# DataLoggerV2.net
KiCad netlist of a schematic drawn in EAGLE
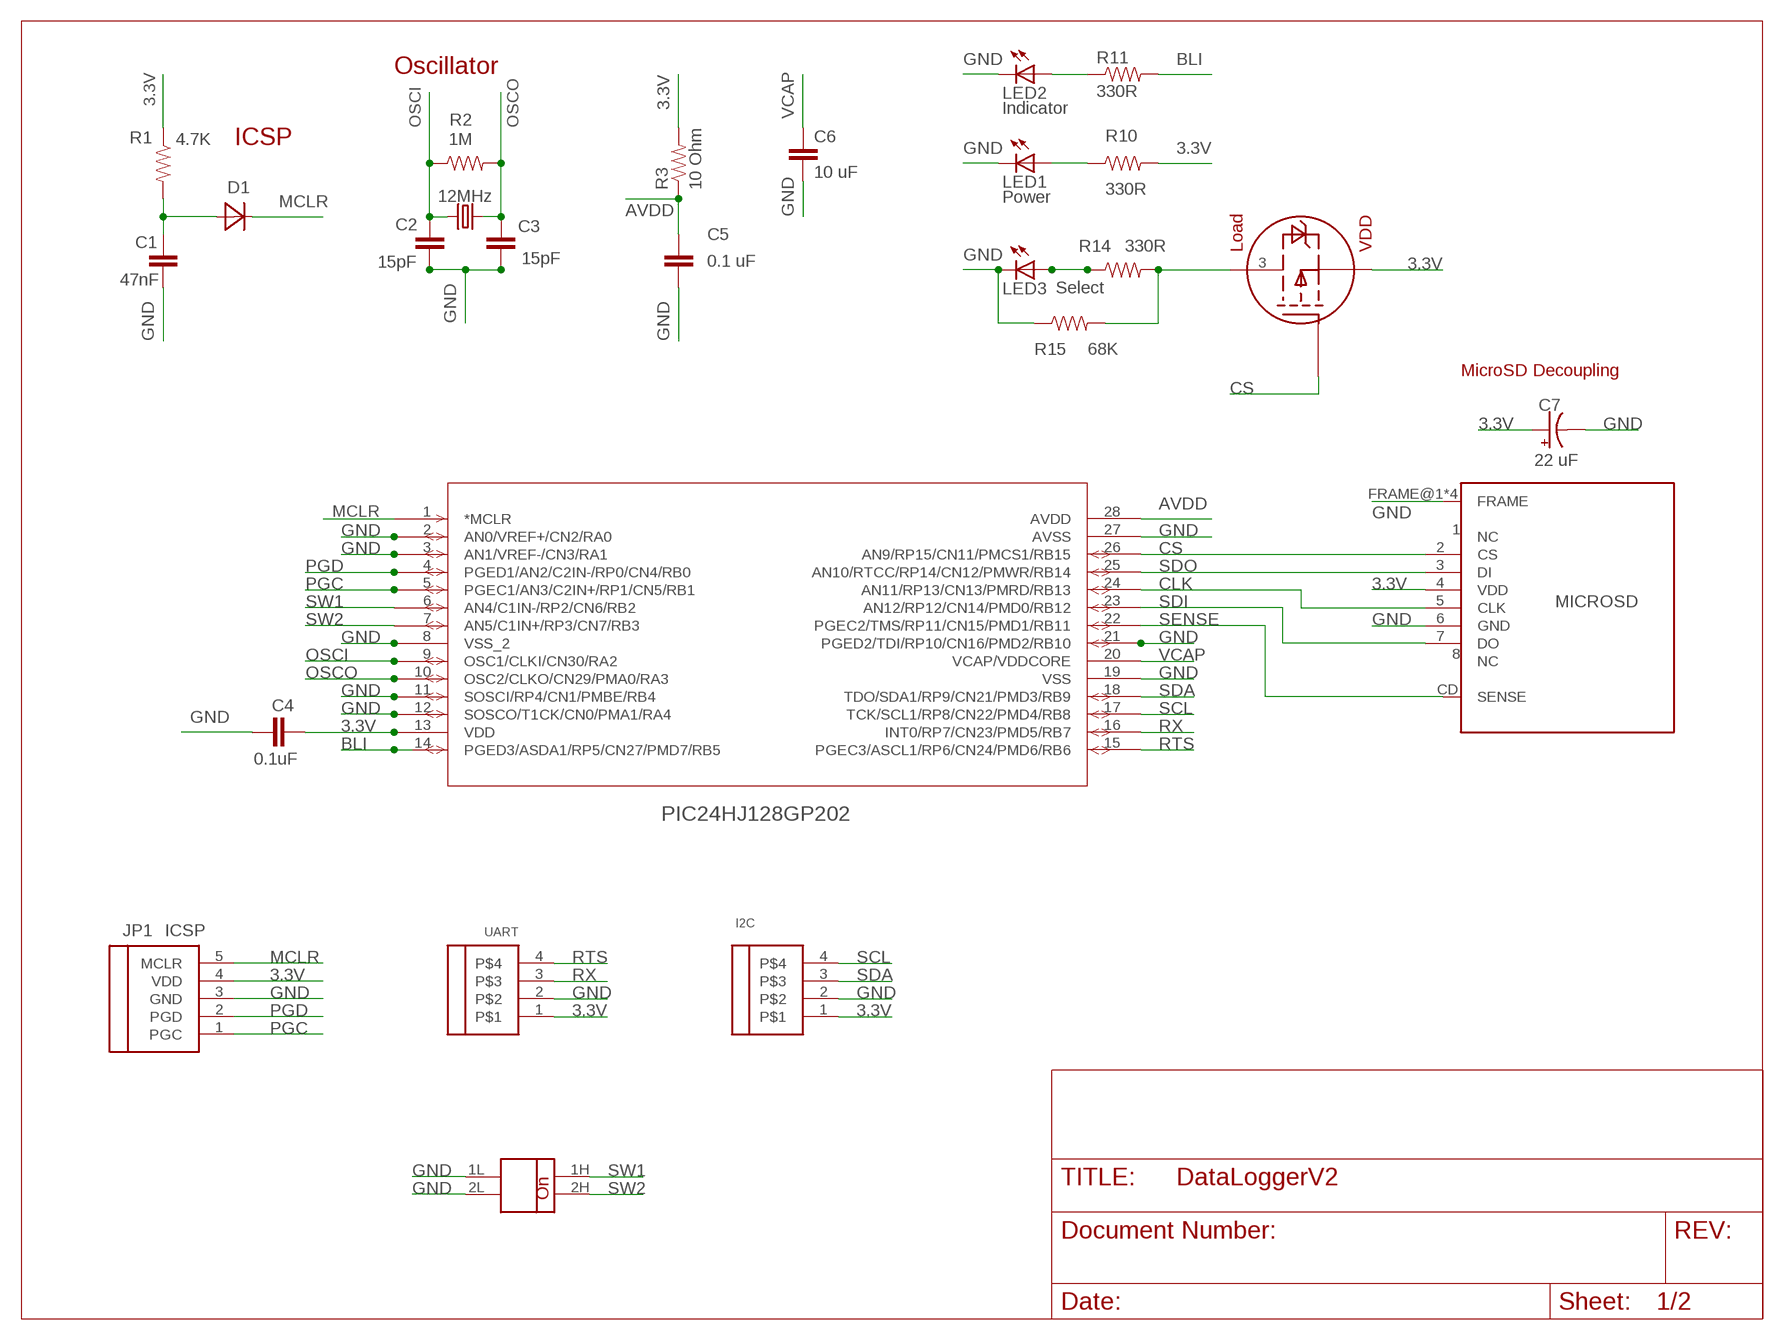
[diagram p0: schematic, sheet 1]
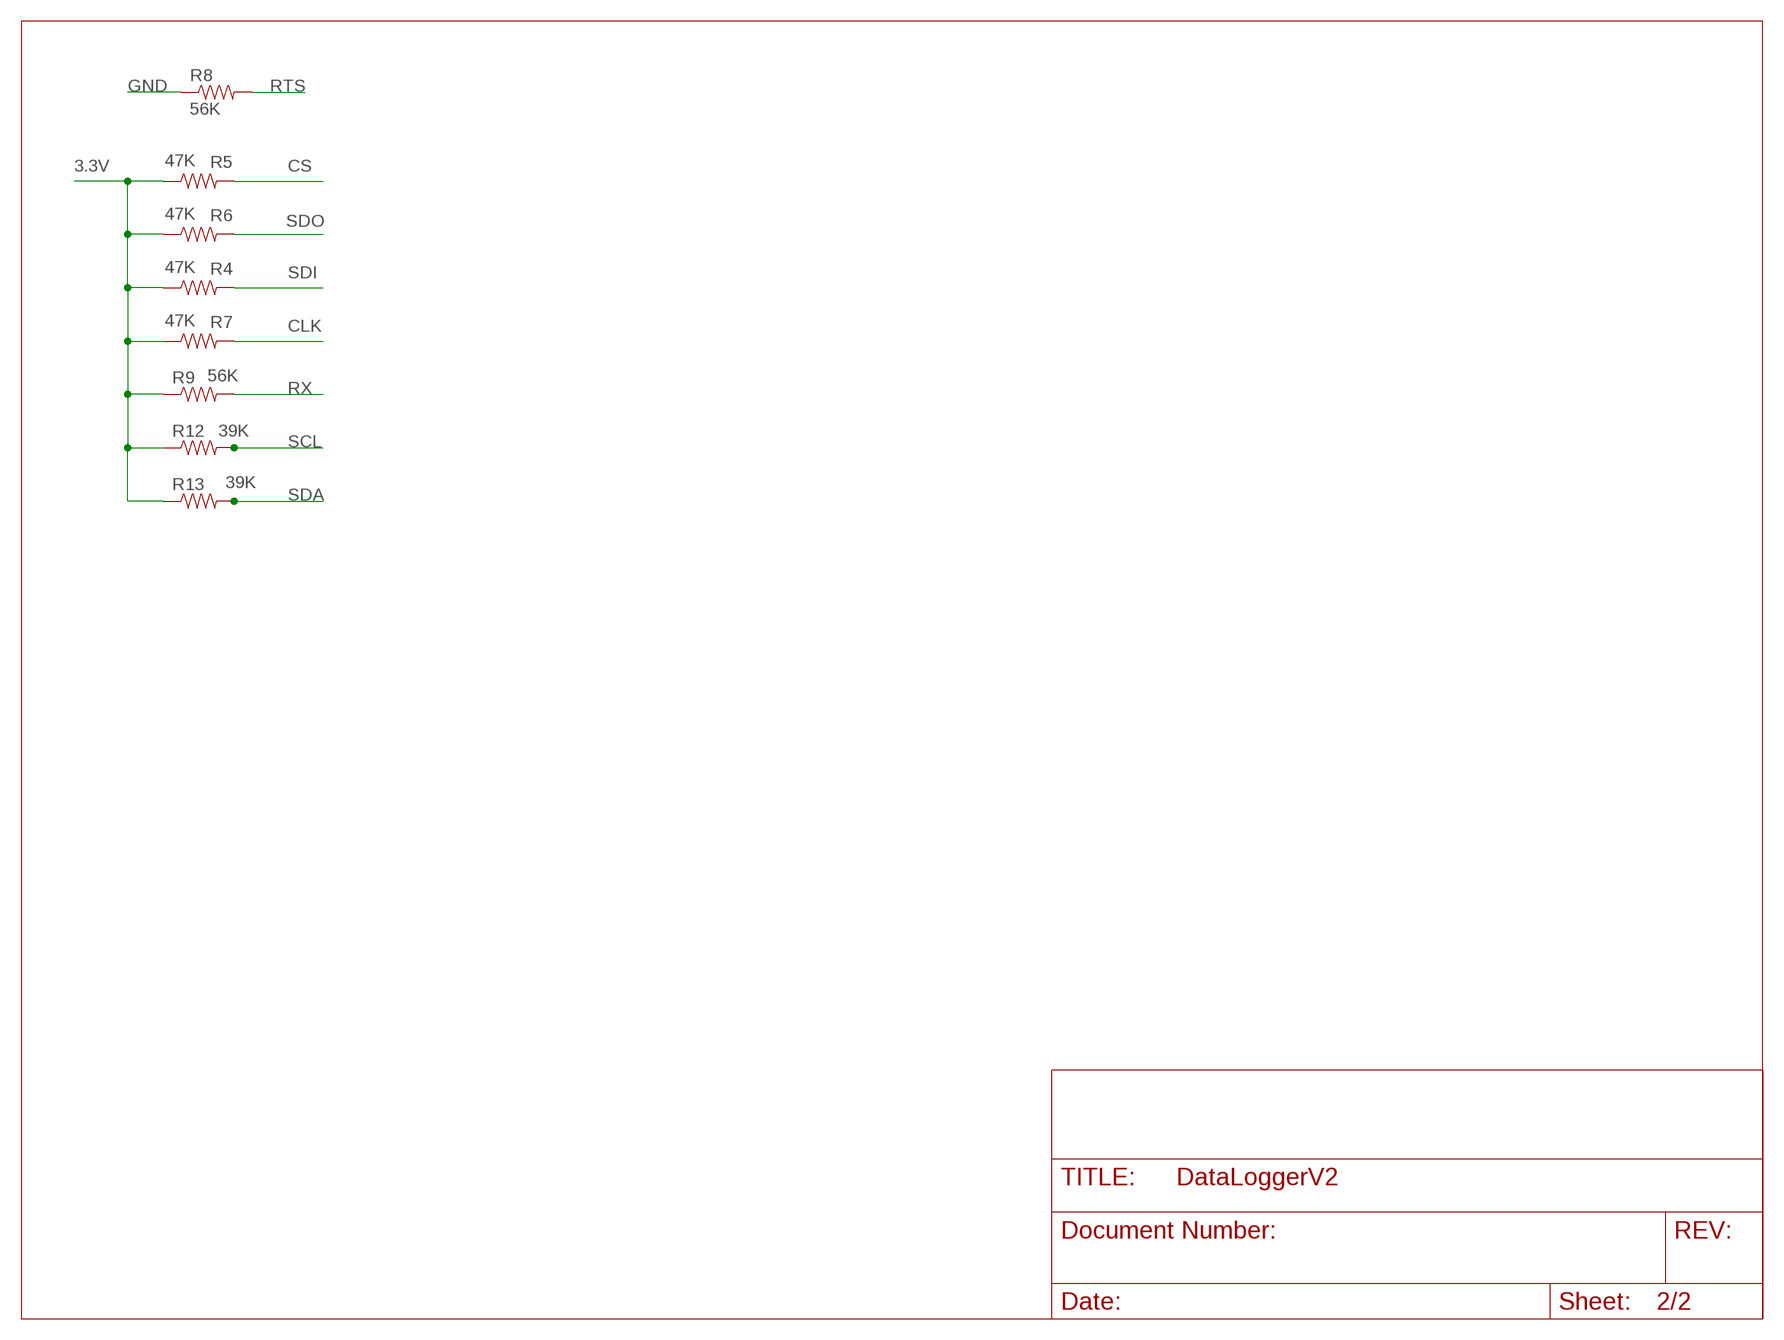
[diagram p1: schematic, sheet 2]

(export (version "E")
  (design (tool "Eeschema 10.0.6"))
  (components
    (comp (ref "C1")
      (value "47nF")
      (footprint "eagle-import:0805_INCH-HS-CAP")
      (libsource (lib "eagle-import") (part "CAP-CERAMIC_0805"))
    )
    (comp (ref "C2")
      (value "15pF")
      (footprint "eagle-import:0805_INCH-HS-CAP")
      (libsource (lib "eagle-import") (part "CAP-CERAMIC_0805"))
    )
    (comp (ref "C3")
      (value "15pF")
      (footprint "eagle-import:0805_INCH-HS-CAP")
      (libsource (lib "eagle-import") (part "CAP-CERAMIC_0805"))
    )
    (comp (ref "C4")
      (value "0.1uF")
      (footprint "eagle-import:0603_INCH-HS-CAP")
      (libsource (lib "eagle-import") (part "CAP-CERAMIC_0603"))
    )
    (comp (ref "C5")
      (value "0.1 uF")
      (footprint "eagle-import:0603_INCH-HS-CAP")
      (libsource (lib "eagle-import") (part "CAP-CERAMIC_0603"))
    )
    (comp (ref "C6")
      (value "10 uF")
      (footprint "eagle-import:1210_INCH-HS-CAP")
      (libsource (lib "eagle-import") (part "CAP-CERAMIC_1210"))
    )
    (comp (ref "C7")
      (value "22 uF")
      (footprint "eagle-import:TANT-C-6032")
      (libsource (lib "eagle-import") (part "CAP-SMD-TANT_C-6032"))
    )
    (comp (ref "D1")
      (value "DIODE_1206")
      (footprint "eagle-import:1206_INCH-HS-DIODE")
      (libsource (lib "eagle-import") (part "DIODE_1206"))
    )
    (comp (ref "I2C")
      (value "HEADER-04_JST-ZH_JST-ZH")
      (footprint "eagle-import:1X04-JST-ZH")
      (libsource (lib "eagle-import") (part "HEADER-04_JST-ZH_JST-ZH"))
    )
    (comp (ref "JP1")
      (value "ICSP")
      (footprint "eagle-import:1X05-JST-ZH")
      (libsource (lib "eagle-import") (part "ICSP_JST-ZH"))
    )
    (comp (ref "LED1")
      (value "Power")
      (footprint "eagle-import:1206_INCH-HS-LED")
      (libsource (lib "eagle-import") (part "LED_SMD_1206"))
    )
    (comp (ref "LED2")
      (value "Indicator")
      (footprint "eagle-import:1206_INCH-HS-LED")
      (libsource (lib "eagle-import") (part "LED_SMD_1206"))
    )
    (comp (ref "LED3")
      (value "Select")
      (footprint "eagle-import:1206_INCH-HS-LED")
      (libsource (lib "eagle-import") (part "LED_SMD_1206"))
    )
    (comp (ref "P-FET")
      (value "NTS2101P")
      (footprint "eagle-import:SOT-323-0NSEMI")
      (libsource (lib "eagle-import") (part "P-MOSFET_SOT323-ONSEMI"))
    )
    (comp (ref "Q1")
      (value "12MHz")
      (footprint "eagle-import:CRYSTAL-SMD-5.0X3.2")
      (libsource (lib "eagle-import") (part "CRYSTAL_SMD-5.0X3.2"))
    )
    (comp (ref "R1")
      (value "4.7K")
      (footprint "eagle-import:0805_INCH-HS")
      (libsource (lib "eagle-import") (part "RESISTOR_0805"))
    )
    (comp (ref "R2")
      (value "1M")
      (footprint "eagle-import:0805_INCH-HS")
      (libsource (lib "eagle-import") (part "RESISTOR_0805"))
    )
    (comp (ref "R3")
      (value "10 Ohm")
      (footprint "eagle-import:0805_INCH-HS")
      (libsource (lib "eagle-import") (part "RESISTOR_0805"))
    )
    (comp (ref "R10")
      (value "330R")
      (footprint "eagle-import:0805_INCH-HS")
      (libsource (lib "eagle-import") (part "RESISTOR_0805"))
    )
    (comp (ref "R11")
      (value "330R")
      (footprint "eagle-import:0805_INCH-HS")
      (libsource (lib "eagle-import") (part "RESISTOR_0805"))
    )
    (comp (ref "R14")
      (value "330R")
      (footprint "eagle-import:0805_INCH-HS")
      (libsource (lib "eagle-import") (part "RESISTOR_0805"))
    )
    (comp (ref "R15")
      (value "68K")
      (footprint "eagle-import:0805_INCH-HS")
      (libsource (lib "eagle-import") (part "RESISTOR_0805"))
    )
    (comp (ref "U$1")
      (value "PIC24HJ128GP202")
      (footprint "eagle-import:SOIC28-W_MC")
      (libsource (lib "eagle-import") (part "PIC24HJ128GP202"))
    )
    (comp (ref "U$2")
      (value "MICROSD")
      (footprint "eagle-import:MICROSD_V1")
      (libsource (lib "eagle-import") (part "MICROSD"))
    )
    (comp (ref "U$3")
      (value "SWITCH-2_HALF-PITCH")
      (footprint "eagle-import:DIP-2-HP")
      (libsource (lib "eagle-import") (part "SWITCH-2_HALF-PITCH"))
    )
    (comp (ref "UART")
      (value "HEADER-04_JST-ZH_JST-ZH")
      (footprint "eagle-import:1X04-JST-ZH")
      (libsource (lib "eagle-import") (part "HEADER-04_JST-ZH_JST-ZH"))
    )
    (comp (ref "R4")
      (value "47K")
      (footprint "eagle-import:0805_INCH-HS")
      (libsource (lib "eagle-import") (part "RESISTOR_0805"))
    )
    (comp (ref "R5")
      (value "47K")
      (footprint "eagle-import:0805_INCH-HS")
      (libsource (lib "eagle-import") (part "RESISTOR_0805"))
    )
    (comp (ref "R6")
      (value "47K")
      (footprint "eagle-import:0805_INCH-HS")
      (libsource (lib "eagle-import") (part "RESISTOR_0805"))
    )
    (comp (ref "R7")
      (value "47K")
      (footprint "eagle-import:0805_INCH-HS")
      (libsource (lib "eagle-import") (part "RESISTOR_0805"))
    )
    (comp (ref "R8")
      (value "56K")
      (footprint "eagle-import:0805_INCH-HS")
      (libsource (lib "eagle-import") (part "RESISTOR_0805"))
    )
    (comp (ref "R9")
      (value "56K")
      (footprint "eagle-import:0805_INCH-HS")
      (libsource (lib "eagle-import") (part "RESISTOR_0805"))
    )
    (comp (ref "R12")
      (value "39K")
      (footprint "eagle-import:0805_INCH-HS")
      (libsource (lib "eagle-import") (part "RESISTOR_0805"))
    )
    (comp (ref "R13")
      (value "39K")
      (footprint "eagle-import:0805_INCH-HS")
      (libsource (lib "eagle-import") (part "RESISTOR_0805"))
    )
  )
  (nets
    (net (code "1") (name "3.3V") (class "Default")
      (node (ref "C4") (pin "1") (pinfunction "1_1") (pintype "passive"))
      (node (ref "C7") (pin "+") (pinfunction "+_+") (pintype "passive"))
      (node (ref "I2C") (pin "1") (pinfunction "P$1_1") (pintype "bidirectional"))
      (node (ref "JP1") (pin "4") (pinfunction "VDD_4") (pintype "bidirectional"))
      (node (ref "P-FET") (pin "2") (pinfunction "S_2") (pintype "bidirectional"))
      (node (ref "R1") (pin "1") (pinfunction "1_1") (pintype "passive"))
      (node (ref "R10") (pin "2") (pinfunction "2_2") (pintype "passive"))
      (node (ref "R12") (pin "1") (pinfunction "1_1") (pintype "passive"))
      (node (ref "R13") (pin "1") (pinfunction "1_1") (pintype "passive"))
      (node (ref "R3") (pin "2") (pinfunction "2_2") (pintype "passive"))
      (node (ref "R4") (pin "1") (pinfunction "1_1") (pintype "passive"))
      (node (ref "R5") (pin "1") (pinfunction "1_1") (pintype "passive"))
      (node (ref "R6") (pin "1") (pinfunction "1_1") (pintype "passive"))
      (node (ref "R7") (pin "1") (pinfunction "1_1") (pintype "passive"))
      (node (ref "R9") (pin "1") (pinfunction "1_1") (pintype "passive"))
      (node (ref "U$1") (pin "13") (pinfunction "VDD_13") (pintype "passive"))
      (node (ref "U$2") (pin "4") (pinfunction "VDD_4") (pintype "power_in"))
      (node (ref "UART") (pin "1") (pinfunction "P$1_1") (pintype "bidirectional"))
    )
    (net (code "2") (name "AVDD") (class "Default")
      (node (ref "C5") (pin "1") (pinfunction "1_1") (pintype "passive"))
      (node (ref "R3") (pin "1") (pinfunction "1_1") (pintype "passive"))
      (node (ref "U$1") (pin "28") (pinfunction "AVDD_28") (pintype "passive"))
    )
    (net (code "3") (name "BLI") (class "Default")
      (node (ref "R11") (pin "2") (pinfunction "2_2") (pintype "passive"))
      (node (ref "U$1") (pin "14") (pinfunction "PGED3/ASDA1/RP5/CN27/PMD7/RB5_14") (pintype "passive"))
    )
    (net (code "4") (name "CLK") (class "Default")
      (node (ref "R7") (pin "2") (pinfunction "2_2") (pintype "passive"))
      (node (ref "U$1") (pin "24") (pinfunction "AN11/RP13/CN13/PMRD/RB13_24") (pintype "passive"))
      (node (ref "U$2") (pin "5") (pinfunction "CLK_5") (pintype "input"))
    )
    (net (code "5") (name "CS") (class "Default")
      (node (ref "P-FET") (pin "1") (pinfunction "G_1") (pintype "input"))
      (node (ref "R5") (pin "2") (pinfunction "2_2") (pintype "passive"))
      (node (ref "U$1") (pin "26") (pinfunction "AN9/RP15/CN11/PMCS1/RB15_26") (pintype "passive"))
      (node (ref "U$2") (pin "2") (pinfunction "CS_2") (pintype "input"))
    )
    (net (code "6") (name "GND") (class "Default")
      (node (ref "C1") (pin "2") (pinfunction "2_2") (pintype "passive"))
      (node (ref "C2") (pin "1") (pinfunction "1_1") (pintype "passive"))
      (node (ref "C3") (pin "1") (pinfunction "1_1") (pintype "passive"))
      (node (ref "C4") (pin "2") (pinfunction "2_2") (pintype "passive"))
      (node (ref "C5") (pin "2") (pinfunction "2_2") (pintype "passive"))
      (node (ref "C6") (pin "P$2") (pinfunction "2_P$2") (pintype "passive"))
      (node (ref "C7") (pin "-") (pinfunction "-_-") (pintype "passive"))
      (node (ref "I2C") (pin "2") (pinfunction "P$2_2") (pintype "bidirectional"))
      (node (ref "JP1") (pin "3") (pinfunction "GND_3") (pintype "bidirectional"))
      (node (ref "LED1") (pin "C") (pinfunction "C_C") (pintype "passive"))
      (node (ref "LED2") (pin "C") (pinfunction "C_C") (pintype "passive"))
      (node (ref "LED3") (pin "C") (pinfunction "C_C") (pintype "passive"))
      (node (ref "R15") (pin "1") (pinfunction "1_1") (pintype "passive"))
      (node (ref "R8") (pin "1") (pinfunction "1_1") (pintype "passive"))
      (node (ref "U$1") (pin "11") (pinfunction "SOSCI/RP4/CN1/PMBE/RB4_11") (pintype "passive"))
      (node (ref "U$1") (pin "12") (pinfunction "SOSCO/T1CK/CN0/PMA1/RA4_12") (pintype "passive"))
      (node (ref "U$1") (pin "19") (pinfunction "VSS_19") (pintype "passive"))
      (node (ref "U$1") (pin "2") (pinfunction "AN0/VREF+/CN2/RA0_2") (pintype "passive"))
      (node (ref "U$1") (pin "21") (pinfunction "PGED2/TDI/RP10/CN16/PMD2/RB10_21") (pintype "passive"))
      (node (ref "U$1") (pin "27") (pinfunction "AVSS_27") (pintype "passive"))
      (node (ref "U$1") (pin "3") (pinfunction "AN1/VREF-/CN3/RA1_3") (pintype "passive"))
      (node (ref "U$1") (pin "8") (pinfunction "VSS_2_8") (pintype "passive"))
      (node (ref "U$2") (pin "6") (pinfunction "GND_6") (pintype "power_in"))
      (node (ref "U$2") (pin "FRAME@1") (pinfunction "FRAME_FRAME@1") (pintype "power_in"))
      (node (ref "U$2") (pin "FRAME@2") (pinfunction "FRAME_FRAME@2") (pintype "power_in"))
      (node (ref "U$2") (pin "FRAME@3") (pinfunction "FRAME_FRAME@3") (pintype "power_in"))
      (node (ref "U$2") (pin "FRAME@4") (pinfunction "FRAME_FRAME@4") (pintype "power_in"))
      (node (ref "U$3") (pin "1L") (pinfunction "1L_1L") (pintype "bidirectional"))
      (node (ref "U$3") (pin "2L") (pinfunction "2L_2L") (pintype "bidirectional"))
      (node (ref "UART") (pin "2") (pinfunction "P$2_2") (pintype "bidirectional"))
    )
    (net (code "7") (name "MCLR") (class "Default")
      (node (ref "D1") (pin "C") (pinfunction "C_C") (pintype "passive"))
      (node (ref "JP1") (pin "5") (pinfunction "MCLR_5") (pintype "bidirectional"))
      (node (ref "U$1") (pin "1") (pinfunction "*MCLR_1") (pintype "passive"))
    )
    (net (code "8") (name "Net-(C1-Pad1)") (class "Default")
      (node (ref "C1") (pin "1") (pinfunction "1_1") (pintype "passive"))
      (node (ref "D1") (pin "A") (pinfunction "A_A") (pintype "passive"))
      (node (ref "R1") (pin "2") (pinfunction "2_2") (pintype "passive"))
    )
    (net (code "9") (name "Net-(LED1-PadA)") (class "Default")
      (node (ref "LED1") (pin "A") (pinfunction "A_A") (pintype "passive"))
      (node (ref "R10") (pin "1") (pinfunction "1_1") (pintype "passive"))
    )
    (net (code "10") (name "Net-(LED2-PadA)") (class "Default")
      (node (ref "LED2") (pin "A") (pinfunction "A_A") (pintype "passive"))
      (node (ref "R11") (pin "1") (pinfunction "1_1") (pintype "passive"))
    )
    (net (code "11") (name "Net-(LED3-PadA)") (class "Default")
      (node (ref "LED3") (pin "A") (pinfunction "A_A") (pintype "passive"))
      (node (ref "R14") (pin "1") (pinfunction "1_1") (pintype "passive"))
    )
    (net (code "12") (name "Net-(P-FET-D)") (class "Default")
      (node (ref "P-FET") (pin "3") (pinfunction "D_3") (pintype "bidirectional"))
      (node (ref "R14") (pin "2") (pinfunction "2_2") (pintype "passive"))
      (node (ref "R15") (pin "2") (pinfunction "2_2") (pintype "passive"))
    )
    (net (code "13") (name "OSCI") (class "Default")
      (node (ref "C2") (pin "2") (pinfunction "2_2") (pintype "passive"))
      (node (ref "Q1") (pin "P$2") (pinfunction "2_P$2") (pintype "passive"))
      (node (ref "R2") (pin "1") (pinfunction "1_1") (pintype "passive"))
      (node (ref "U$1") (pin "9") (pinfunction "OSC1/CLKI/CN30/RA2_9") (pintype "passive"))
    )
    (net (code "14") (name "OSCO") (class "Default")
      (node (ref "C3") (pin "2") (pinfunction "2_2") (pintype "passive"))
      (node (ref "Q1") (pin "P$1") (pinfunction "1_P$1") (pintype "passive"))
      (node (ref "R2") (pin "2") (pinfunction "2_2") (pintype "passive"))
      (node (ref "U$1") (pin "10") (pinfunction "OSC2/CLKO/CN29/PMA0/RA3_10") (pintype "passive"))
    )
    (net (code "15") (name "PGC") (class "Default")
      (node (ref "JP1") (pin "1") (pinfunction "PGC_1") (pintype "bidirectional"))
      (node (ref "U$1") (pin "5") (pinfunction "PGEC1/AN3/C2IN+/RP1/CN5/RB1_5") (pintype "passive"))
    )
    (net (code "16") (name "PGD") (class "Default")
      (node (ref "JP1") (pin "2") (pinfunction "PGD_2") (pintype "bidirectional"))
      (node (ref "U$1") (pin "4") (pinfunction "PGED1/AN2/C2IN-/RP0/CN4/RB0_4") (pintype "passive"))
    )
    (net (code "17") (name "RTS") (class "Default")
      (node (ref "R8") (pin "2") (pinfunction "2_2") (pintype "passive"))
      (node (ref "U$1") (pin "15") (pinfunction "PGEC3/ASCL1/RP6/CN24/PMD6/RB6_15") (pintype "passive"))
      (node (ref "UART") (pin "4") (pinfunction "P$4_4") (pintype "bidirectional"))
    )
    (net (code "18") (name "RX") (class "Default")
      (node (ref "R9") (pin "2") (pinfunction "2_2") (pintype "passive"))
      (node (ref "U$1") (pin "16") (pinfunction "INT0/RP7/CN23/PMD5/RB7_16") (pintype "passive"))
      (node (ref "UART") (pin "3") (pinfunction "P$3_3") (pintype "bidirectional"))
    )
    (net (code "19") (name "SCL") (class "Default")
      (node (ref "I2C") (pin "4") (pinfunction "P$4_4") (pintype "bidirectional"))
      (node (ref "R12") (pin "2") (pinfunction "2_2") (pintype "passive"))
      (node (ref "U$1") (pin "17") (pinfunction "TCK/SCL1/RP8/CN22/PMD4/RB8_17") (pintype "passive"))
    )
    (net (code "20") (name "SDA") (class "Default")
      (node (ref "I2C") (pin "3") (pinfunction "P$3_3") (pintype "bidirectional"))
      (node (ref "R13") (pin "2") (pinfunction "2_2") (pintype "passive"))
      (node (ref "U$1") (pin "18") (pinfunction "TDO/SDA1/RP9/CN21/PMD3/RB9_18") (pintype "passive"))
    )
    (net (code "21") (name "SDI") (class "Default")
      (node (ref "R4") (pin "2") (pinfunction "2_2") (pintype "passive"))
      (node (ref "U$1") (pin "23") (pinfunction "AN12/RP12/CN14/PMD0/RB12_23") (pintype "passive"))
      (node (ref "U$2") (pin "7") (pinfunction "DO_7") (pintype "output"))
    )
    (net (code "22") (name "SDO") (class "Default")
      (node (ref "R6") (pin "2") (pinfunction "2_2") (pintype "passive"))
      (node (ref "U$1") (pin "25") (pinfunction "AN10/RTCC/RP14/CN12/PMWR/RB14_25") (pintype "passive"))
      (node (ref "U$2") (pin "3") (pinfunction "DI_3") (pintype "input"))
    )
    (net (code "23") (name "SENSE") (class "Default")
      (node (ref "U$1") (pin "22") (pinfunction "PGEC2/TMS/RP11/CN15/PMD1/RB11_22") (pintype "passive"))
      (node (ref "U$2") (pin "CD") (pinfunction "SENSE_CD") (pintype "output"))
    )
    (net (code "24") (name "SW1") (class "Default")
      (node (ref "U$1") (pin "6") (pinfunction "AN4/C1IN-/RP2/CN6/RB2_6") (pintype "passive"))
      (node (ref "U$3") (pin "1H") (pinfunction "1H_1H") (pintype "bidirectional"))
    )
    (net (code "25") (name "SW2") (class "Default")
      (node (ref "U$1") (pin "7") (pinfunction "AN5/C1IN+/RP3/CN7/RB3_7") (pintype "passive"))
      (node (ref "U$3") (pin "2H") (pinfunction "2H_2H") (pintype "bidirectional"))
    )
    (net (code "26") (name "VCAP") (class "Default")
      (node (ref "C6") (pin "P$1") (pinfunction "1_P$1") (pintype "passive"))
      (node (ref "U$1") (pin "20") (pinfunction "VCAP/VDDCORE_20") (pintype "passive"))
    )
    (net (code "27") (name "unconnected-(U$2-NC-Pad1)") (class "Default")
      (node (ref "U$2") (pin "1") (pinfunction "NC_1") (pintype "no_connect"))
    )
    (net (code "28") (name "unconnected-(U$2-NC-Pad8)") (class "Default")
      (node (ref "U$2") (pin "8") (pinfunction "NC_8") (pintype "no_connect"))
    )
  )
)
